# vco1_components.net
KiCad netlist of a schematic drawn in EAGLE
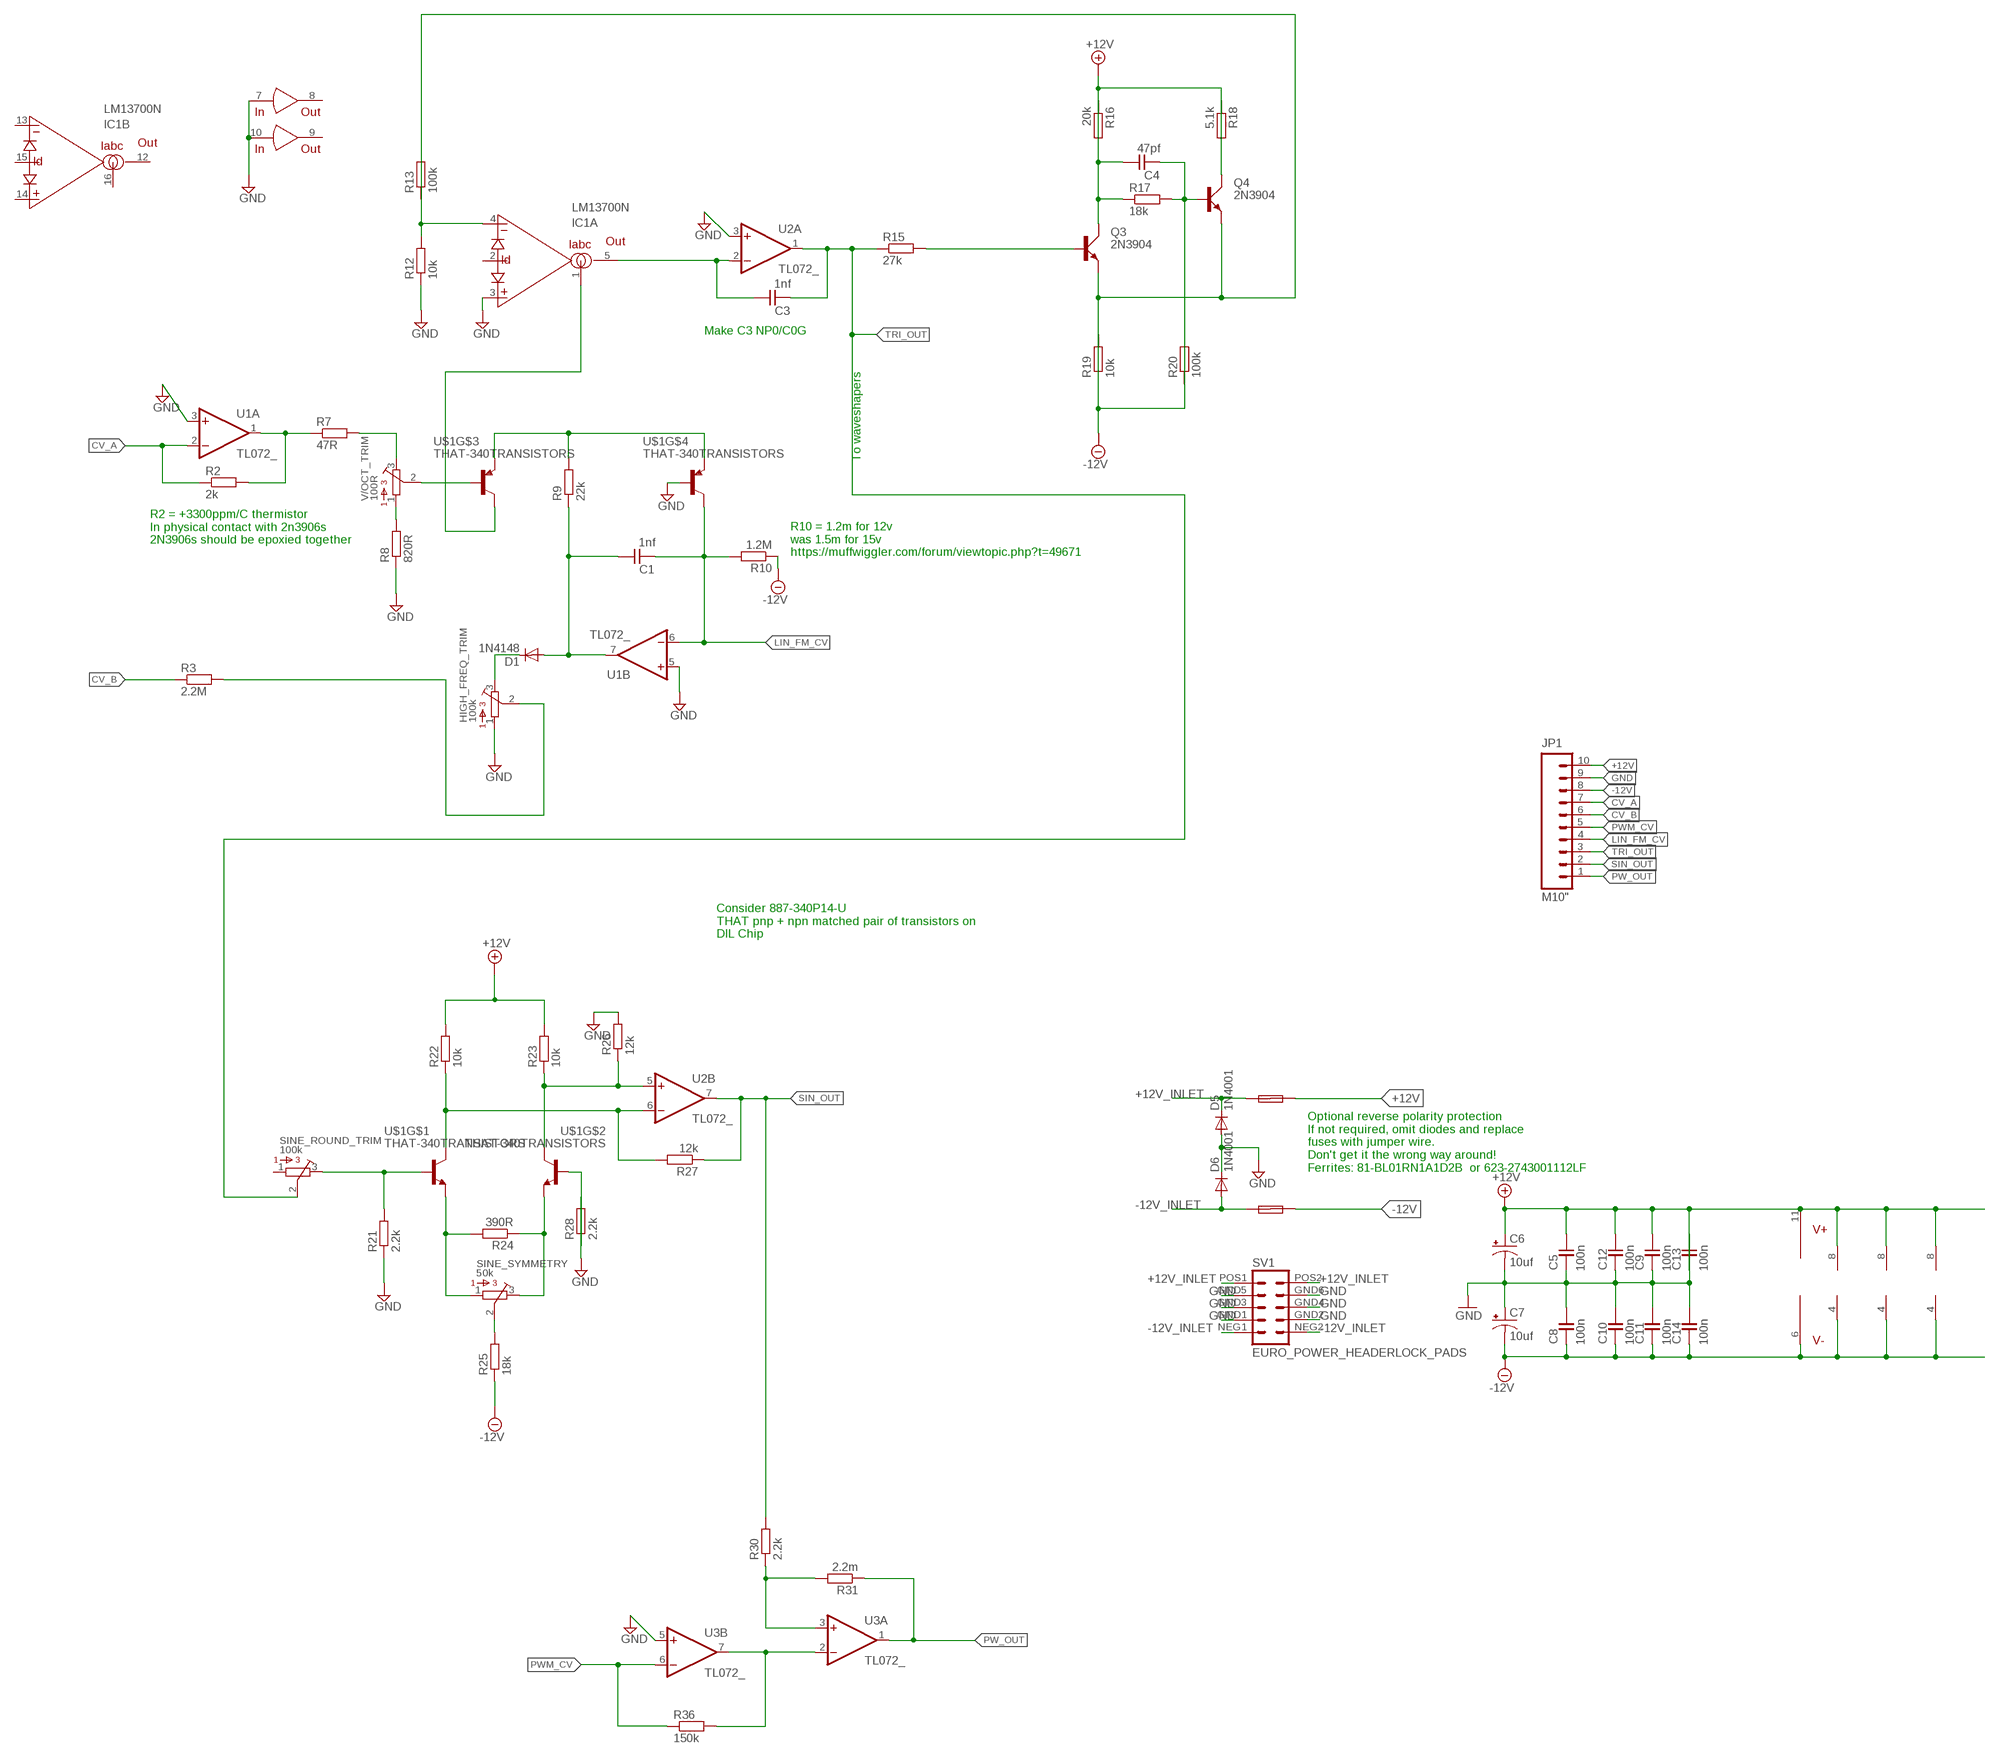
[diagram p0: schematic, sheet 1]

(export (version "E")
  (design (tool "Eeschema 10.0.6"))
  (components
    (comp (ref "C1")
      (value "1nf")
      (footprint "eagle-import:C050-024X044")
      (libsource (lib "eagle-import") (part "C-EU050-024X044"))
    )
    (comp (ref "C3")
      (value "1nf")
      (footprint "eagle-import:C050-024X044")
      (libsource (lib "eagle-import") (part "C-EU050-024X044"))
    )
    (comp (ref "C4")
      (value "47pf")
      (footprint "eagle-import:C050-024X044")
      (libsource (lib "eagle-import") (part "C-EU050-024X044"))
    )
    (comp (ref "C5")
      (value "100n")
      (footprint "eagle-import:C050-024X044")
      (libsource (lib "eagle-import") (part "C-EU050-024X044"))
    )
    (comp (ref "C6")
      (value "10uf")
      (footprint "eagle-import:CPOL-RADIAL-10UF-25V")
      (libsource (lib "eagle-import") (part "CAP_POLPTH2"))
    )
    (comp (ref "C7")
      (value "10uf")
      (footprint "eagle-import:CPOL-RADIAL-10UF-25V")
      (libsource (lib "eagle-import") (part "CAP_POLPTH2"))
    )
    (comp (ref "C8")
      (value "100n")
      (footprint "eagle-import:C050-024X044")
      (libsource (lib "eagle-import") (part "C-EU050-024X044"))
    )
    (comp (ref "C9")
      (value "100n")
      (footprint "eagle-import:C050-024X044")
      (libsource (lib "eagle-import") (part "C-EU050-024X044"))
    )
    (comp (ref "C10")
      (value "100n")
      (footprint "eagle-import:C050-024X044")
      (libsource (lib "eagle-import") (part "C-EU050-024X044"))
    )
    (comp (ref "C11")
      (value "100n")
      (footprint "eagle-import:C050-024X044")
      (libsource (lib "eagle-import") (part "C-EU050-024X044"))
    )
    (comp (ref "C12")
      (value "100n")
      (footprint "eagle-import:C050-024X044")
      (libsource (lib "eagle-import") (part "C-EU050-024X044"))
    )
    (comp (ref "C13")
      (value "100n")
      (footprint "eagle-import:C050-024X044")
      (libsource (lib "eagle-import") (part "C-EU050-024X044"))
    )
    (comp (ref "C14")
      (value "100n")
      (footprint "eagle-import:C050-024X044")
      (libsource (lib "eagle-import") (part "C-EU050-024X044"))
    )
    (comp (ref "D1")
      (value "1N4148")
      (footprint "eagle-import:DO35-7")
      (libsource (lib "eagle-import") (part "SMALL_DIODEDO35-7"))
    )
    (comp (ref "D5")
      (value "1N4001")
      (footprint "eagle-import:DO41-10")
      (libsource (lib "eagle-import") (part "1N4004"))
    )
    (comp (ref "D6")
      (value "1N4001")
      (footprint "eagle-import:DO41-10")
      (libsource (lib "eagle-import") (part "1N4004"))
    )
    (comp (ref "F1")
      (value "FUSE")
      (footprint "eagle-import:C050H075X075")
      (libsource (lib "eagle-import") (part "PTC_FUSEPOLY_FUSE"))
    )
    (comp (ref "F2")
      (value "FUSE")
      (footprint "eagle-import:C050H075X075")
      (libsource (lib "eagle-import") (part "PTC_FUSEPOLY_FUSE"))
    )
    (comp (ref "HIGH_FREQ_TRIM")
      (value "100k")
      (footprint "eagle-import:BOURNS_3362P_TRIMMER")
      (libsource (lib "eagle-import") (part "BOURNS_3362P_TRIMMERP"))
    )
    (comp (ref "IC1")
      (value "LM13700N")
      (footprint "eagle-import:DIL16")
      (libsource (lib "eagle-import") (part "LM13700N"))
    )
    (comp (ref "JP1")
      (value "M10\"")
      (footprint "eagle-import:1X10")
      (libsource (lib "eagle-import") (part "M10{dblquote}"))
    )
    (comp (ref "Q3")
      (value "2N3904")
      (footprint "eagle-import:TO92D")
      (libsource (lib "eagle-import") (part "2N3904"))
    )
    (comp (ref "Q4")
      (value "2N3904")
      (footprint "eagle-import:TO92D")
      (libsource (lib "eagle-import") (part "2N3904"))
    )
    (comp (ref "R2")
      (value "2k")
      (footprint "eagle-import:7MM_RESISTOR")
      (libsource (lib "eagle-import") (part "RESISTOR7MM"))
    )
    (comp (ref "R3")
      (value "2.2M")
      (footprint "eagle-import:7MM_RESISTOR")
      (libsource (lib "eagle-import") (part "RESISTOR7MM"))
    )
    (comp (ref "R7")
      (value "47R")
      (footprint "eagle-import:7MM_RESISTOR")
      (libsource (lib "eagle-import") (part "RESISTOR7MM"))
    )
    (comp (ref "R8")
      (value "820R")
      (footprint "eagle-import:7MM_RESISTOR")
      (libsource (lib "eagle-import") (part "RESISTOR7MM"))
    )
    (comp (ref "R9")
      (value "22k")
      (footprint "eagle-import:7MM_RESISTOR")
      (libsource (lib "eagle-import") (part "RESISTOR7MM"))
    )
    (comp (ref "R10")
      (value "1.2M")
      (footprint "eagle-import:7MM_RESISTOR")
      (libsource (lib "eagle-import") (part "RESISTOR7MM"))
    )
    (comp (ref "R12")
      (value "10k")
      (footprint "eagle-import:7MM_RESISTOR")
      (libsource (lib "eagle-import") (part "RESISTOR7MM"))
    )
    (comp (ref "R13")
      (value "100k")
      (footprint "eagle-import:7MM_RESISTOR")
      (libsource (lib "eagle-import") (part "RESISTOR7MM"))
    )
    (comp (ref "R15")
      (value "27k")
      (footprint "eagle-import:7MM_RESISTOR")
      (libsource (lib "eagle-import") (part "RESISTOR7MM"))
    )
    (comp (ref "R16")
      (value "20k")
      (footprint "eagle-import:7MM_RESISTOR")
      (libsource (lib "eagle-import") (part "RESISTOR7MM"))
    )
    (comp (ref "R17")
      (value "18k")
      (footprint "eagle-import:7MM_RESISTOR")
      (libsource (lib "eagle-import") (part "RESISTOR7MM"))
    )
    (comp (ref "R18")
      (value "5.1k")
      (footprint "eagle-import:7MM_RESISTOR")
      (libsource (lib "eagle-import") (part "RESISTOR7MM"))
    )
    (comp (ref "R19")
      (value "10k")
      (footprint "eagle-import:7MM_RESISTOR")
      (libsource (lib "eagle-import") (part "RESISTOR7MM"))
    )
    (comp (ref "R20")
      (value "100k")
      (footprint "eagle-import:7MM_RESISTOR")
      (libsource (lib "eagle-import") (part "RESISTOR7MM"))
    )
    (comp (ref "R21")
      (value "2.2k")
      (footprint "eagle-import:7MM_RESISTOR")
      (libsource (lib "eagle-import") (part "RESISTOR7MM"))
    )
    (comp (ref "R22")
      (value "10k")
      (footprint "eagle-import:7MM_RESISTOR")
      (libsource (lib "eagle-import") (part "RESISTOR7MM"))
    )
    (comp (ref "R23")
      (value "10k")
      (footprint "eagle-import:7MM_RESISTOR")
      (libsource (lib "eagle-import") (part "RESISTOR7MM"))
    )
    (comp (ref "R24")
      (value "390R")
      (footprint "eagle-import:7MM_RESISTOR")
      (libsource (lib "eagle-import") (part "RESISTOR7MM"))
    )
    (comp (ref "R25")
      (value "18k")
      (footprint "eagle-import:7MM_RESISTOR")
      (libsource (lib "eagle-import") (part "RESISTOR7MM"))
    )
    (comp (ref "R26")
      (value "12k")
      (footprint "eagle-import:7MM_RESISTOR")
      (libsource (lib "eagle-import") (part "RESISTOR7MM"))
    )
    (comp (ref "R27")
      (value "12k")
      (footprint "eagle-import:7MM_RESISTOR")
      (libsource (lib "eagle-import") (part "RESISTOR7MM"))
    )
    (comp (ref "R28")
      (value "2.2k")
      (footprint "eagle-import:7MM_RESISTOR")
      (libsource (lib "eagle-import") (part "RESISTOR7MM"))
    )
    (comp (ref "R30")
      (value "2.2k")
      (footprint "eagle-import:7MM_RESISTOR")
      (libsource (lib "eagle-import") (part "RESISTOR7MM"))
    )
    (comp (ref "R31")
      (value "2.2m")
      (footprint "eagle-import:7MM_RESISTOR")
      (libsource (lib "eagle-import") (part "RESISTOR7MM"))
    )
    (comp (ref "R36")
      (value "150k")
      (footprint "eagle-import:7MM_RESISTOR")
      (libsource (lib "eagle-import") (part "RESISTOR7MM"))
    )
    (comp (ref "SINE_ROUND_TRIM")
      (value "100k")
      (footprint "eagle-import:BOURNS_3362P_TRIMMER")
      (libsource (lib "eagle-import") (part "BOURNS_3362P_TRIMMERP"))
    )
    (comp (ref "SINE_SYMMETRY")
      (value "50k")
      (footprint "eagle-import:BOURNS_3362P_TRIMMER")
      (libsource (lib "eagle-import") (part "BOURNS_3362P_TRIMMERP"))
    )
    (comp (ref "SV1")
      (value "EURO_POWER_HEADERLOCK_PADS")
      (footprint "eagle-import:EURO_PWR_HEADER_LOCK")
      (libsource (lib "eagle-import") (part "EURO_POWER_HEADERLOCK_PADS"))
    )
    (comp (ref "U$1")
      (value "THAT-340TRANSISTORS")
      (footprint "eagle-import:THAT340")
      (libsource (lib "eagle-import") (part "THAT-340TRANSISTORS"))
    )
    (comp (ref "U1")
      (value "TL072_")
      (footprint "eagle-import:DIL08")
      (libsource (lib "eagle-import") (part "TL072_"))
    )
    (comp (ref "U2")
      (value "TL072_")
      (footprint "eagle-import:DIL08")
      (libsource (lib "eagle-import") (part "TL072_"))
    )
    (comp (ref "U3")
      (value "TL072_")
      (footprint "eagle-import:DIL08")
      (libsource (lib "eagle-import") (part "TL072_"))
    )
    (comp (ref "V/OCT_TRIM")
      (value "100R")
      (footprint "eagle-import:BOURNS_3362P_TRIMMER")
      (libsource (lib "eagle-import") (part "BOURNS_3362P_TRIMMERP"))
    )
  )
  (nets
    (net (code "1") (name "+12V") (class "Default")
      (node (ref "C12") (pin "1") (pinfunction "1_1") (pintype "passive"))
      (node (ref "C13") (pin "2") (pinfunction "2_2") (pintype "passive"))
      (node (ref "C5") (pin "1") (pinfunction "1_1") (pintype "passive"))
      (node (ref "C6") (pin "1") (pinfunction "+_1") (pintype "passive"))
      (node (ref "C9") (pin "1") (pinfunction "1_1") (pintype "passive"))
      (node (ref "F1") (pin "2") (pinfunction "P$2_2") (pintype "bidirectional"))
      (node (ref "IC1") (pin "11") (pinfunction "V+_11") (pintype "bidirectional"))
      (node (ref "JP1") (pin "10") (pinfunction "10_10") (pintype "passive"))
      (node (ref "R16") (pin "2") (pinfunction "2_2") (pintype "passive"))
      (node (ref "R18") (pin "2") (pinfunction "2_2") (pintype "passive"))
      (node (ref "R22") (pin "2") (pinfunction "2_2") (pintype "passive"))
      (node (ref "R23") (pin "2") (pinfunction "2_2") (pintype "passive"))
      (node (ref "U1") (pin "8") (pinfunction "V+_8") (pintype "power_in"))
      (node (ref "U2") (pin "8") (pinfunction "V+_8") (pintype "power_in"))
      (node (ref "U3") (pin "8") (pinfunction "V+_8") (pintype "power_in"))
    )
    (net (code "2") (name "-12V") (class "Default")
      (node (ref "C10") (pin "2") (pinfunction "2_2") (pintype "passive"))
      (node (ref "C11") (pin "2") (pinfunction "2_2") (pintype "passive"))
      (node (ref "C14") (pin "2") (pinfunction "2_2") (pintype "passive"))
      (node (ref "C7") (pin "2") (pinfunction "-_2") (pintype "passive"))
      (node (ref "C8") (pin "2") (pinfunction "2_2") (pintype "passive"))
      (node (ref "F2") (pin "2") (pinfunction "P$2_2") (pintype "bidirectional"))
      (node (ref "IC1") (pin "6") (pinfunction "V-_6") (pintype "bidirectional"))
      (node (ref "JP1") (pin "8") (pinfunction "8_8") (pintype "passive"))
      (node (ref "R10") (pin "1") (pinfunction "1_1") (pintype "passive"))
      (node (ref "R19") (pin "2") (pinfunction "2_2") (pintype "passive"))
      (node (ref "R20") (pin "2") (pinfunction "2_2") (pintype "passive"))
      (node (ref "R25") (pin "1") (pinfunction "1_1") (pintype "passive"))
      (node (ref "U1") (pin "4") (pinfunction "V-_4") (pintype "power_in"))
      (node (ref "U2") (pin "4") (pinfunction "V-_4") (pintype "power_in"))
      (node (ref "U3") (pin "4") (pinfunction "V-_4") (pintype "power_in"))
    )
    (net (code "3") (name "/+12V_INLET") (class "Default")
      (node (ref "D5") (pin "C") (pinfunction "C_C") (pintype "passive"))
      (node (ref "F1") (pin "1") (pinfunction "P$1_1") (pintype "bidirectional"))
      (node (ref "SV1") (pin "POS1") (pinfunction "10_POS1") (pintype "passive"))
      (node (ref "SV1") (pin "POS2") (pinfunction "9_POS2") (pintype "passive"))
    )
    (net (code "4") (name "/-12V_INLET") (class "Default")
      (node (ref "D6") (pin "A") (pinfunction "A_A") (pintype "passive"))
      (node (ref "F2") (pin "1") (pinfunction "P$1_1") (pintype "bidirectional"))
      (node (ref "SV1") (pin "NEG1") (pinfunction "2_NEG1") (pintype "passive"))
      (node (ref "SV1") (pin "NEG2") (pinfunction "1_NEG2") (pintype "passive"))
    )
    (net (code "5") (name "CV_A") (class "Default")
      (node (ref "JP1") (pin "7") (pinfunction "7_7") (pintype "passive"))
      (node (ref "R2") (pin "1") (pinfunction "1_1") (pintype "passive"))
      (node (ref "U1") (pin "2") (pinfunction "-IN_2") (pintype "input"))
    )
    (net (code "6") (name "CV_B") (class "Default")
      (node (ref "JP1") (pin "6") (pinfunction "6_6") (pintype "passive"))
      (node (ref "R3") (pin "1") (pinfunction "1_1") (pintype "passive"))
    )
    (net (code "7") (name "GND") (class "Default")
      (node (ref "C10") (pin "1") (pinfunction "1_1") (pintype "passive"))
      (node (ref "C11") (pin "1") (pinfunction "1_1") (pintype "passive"))
      (node (ref "C12") (pin "2") (pinfunction "2_2") (pintype "passive"))
      (node (ref "C13") (pin "1") (pinfunction "1_1") (pintype "passive"))
      (node (ref "C14") (pin "1") (pinfunction "1_1") (pintype "passive"))
      (node (ref "C5") (pin "2") (pinfunction "2_2") (pintype "passive"))
      (node (ref "C6") (pin "2") (pinfunction "-_2") (pintype "passive"))
      (node (ref "C7") (pin "1") (pinfunction "+_1") (pintype "passive"))
      (node (ref "C8") (pin "1") (pinfunction "1_1") (pintype "passive"))
      (node (ref "C9") (pin "2") (pinfunction "2_2") (pintype "passive"))
      (node (ref "D5") (pin "A") (pinfunction "A_A") (pintype "passive"))
      (node (ref "D6") (pin "C") (pinfunction "C_C") (pintype "passive"))
      (node (ref "HIGH_FREQ_TRIM") (pin "1") (pinfunction "1_1") (pintype "passive"))
      (node (ref "IC1") (pin "10") (pinfunction "IN_10") (pintype "bidirectional"))
      (node (ref "IC1") (pin "3") (pinfunction "+IN_3") (pintype "bidirectional"))
      (node (ref "IC1") (pin "7") (pinfunction "IN_7") (pintype "bidirectional"))
      (node (ref "JP1") (pin "9") (pinfunction "9_9") (pintype "passive"))
      (node (ref "R12") (pin "1") (pinfunction "1_1") (pintype "passive"))
      (node (ref "R21") (pin "1") (pinfunction "1_1") (pintype "passive"))
      (node (ref "R26") (pin "2") (pinfunction "2_2") (pintype "passive"))
      (node (ref "R28") (pin "2") (pinfunction "2_2") (pintype "passive"))
      (node (ref "R8") (pin "1") (pinfunction "1_1") (pintype "passive"))
      (node (ref "SV1") (pin "GND1") (pinfunction "4_GND1") (pintype "passive"))
      (node (ref "SV1") (pin "GND2") (pinfunction "3_GND2") (pintype "passive"))
      (node (ref "SV1") (pin "GND3") (pinfunction "6_GND3") (pintype "passive"))
      (node (ref "SV1") (pin "GND4") (pinfunction "5_GND4") (pintype "passive"))
      (node (ref "SV1") (pin "GND5") (pinfunction "8_GND5") (pintype "passive"))
      (node (ref "SV1") (pin "GND6") (pinfunction "7_GND6") (pintype "passive"))
      (node (ref "U$1") (pin "9") (pinfunction "B_9") (pintype "passive"))
      (node (ref "U1") (pin "3") (pinfunction "+IN_3") (pintype "input"))
      (node (ref "U1") (pin "5") (pinfunction "+IN_5") (pintype "input"))
      (node (ref "U2") (pin "3") (pinfunction "+IN_3") (pintype "input"))
      (node (ref "U3") (pin "5") (pinfunction "+IN_5") (pintype "input"))
    )
    (net (code "8") (name "LIN_FM_CV") (class "Default")
      (node (ref "C1") (pin "2") (pinfunction "2_2") (pintype "passive"))
      (node (ref "JP1") (pin "4") (pinfunction "4_4") (pintype "passive"))
      (node (ref "R10") (pin "2") (pinfunction "2_2") (pintype "passive"))
      (node (ref "U$1") (pin "8") (pinfunction "C_8") (pintype "passive"))
      (node (ref "U1") (pin "6") (pinfunction "-IN_6") (pintype "input"))
    )
    (net (code "9") (name "Net-(C4-Pad1)") (class "Default")
      (node (ref "C4") (pin "1") (pinfunction "1_1") (pintype "passive"))
      (node (ref "Q3") (pin "C") (pinfunction "C_C") (pintype "passive"))
      (node (ref "R16") (pin "1") (pinfunction "1_1") (pintype "passive"))
      (node (ref "R17") (pin "1") (pinfunction "1_1") (pintype "passive"))
    )
    (net (code "10") (name "Net-(C4-Pad2)") (class "Default")
      (node (ref "C4") (pin "2") (pinfunction "2_2") (pintype "passive"))
      (node (ref "Q4") (pin "B") (pinfunction "B_B") (pintype "passive"))
      (node (ref "R17") (pin "2") (pinfunction "2_2") (pintype "passive"))
      (node (ref "R20") (pin "1") (pinfunction "1_1") (pintype "passive"))
    )
    (net (code "11") (name "Net-(D1-PadC)") (class "Default")
      (node (ref "D1") (pin "C") (pinfunction "C_C") (pintype "passive"))
      (node (ref "HIGH_FREQ_TRIM") (pin "3") (pinfunction "3_3") (pintype "passive"))
    )
    (net (code "12") (name "Net-(HIGH_FREQ_TRIM-Pad2)") (class "Default")
      (node (ref "HIGH_FREQ_TRIM") (pin "2") (pinfunction "2_2") (pintype "passive"))
      (node (ref "R3") (pin "2") (pinfunction "2_2") (pintype "passive"))
    )
    (net (code "13") (name "Net-(IC1A--IN)") (class "Default")
      (node (ref "IC1") (pin "4") (pinfunction "-IN_4") (pintype "bidirectional"))
      (node (ref "R12") (pin "2") (pinfunction "2_2") (pintype "passive"))
      (node (ref "R13") (pin "2") (pinfunction "2_2") (pintype "passive"))
    )
    (net (code "14") (name "Net-(IC1A-IABC)") (class "Default")
      (node (ref "IC1") (pin "1") (pinfunction "IABC_1") (pintype "bidirectional"))
      (node (ref "U$1") (pin "7") (pinfunction "C_7") (pintype "passive"))
    )
    (net (code "15") (name "Net-(IC1A-OUT)") (class "Default")
      (node (ref "C3") (pin "1") (pinfunction "1_1") (pintype "passive"))
      (node (ref "IC1") (pin "5") (pinfunction "OUT_5") (pintype "bidirectional"))
      (node (ref "U2") (pin "2") (pinfunction "-IN_2") (pintype "input"))
    )
    (net (code "16") (name "Net-(Q3-PadB)") (class "Default")
      (node (ref "Q3") (pin "B") (pinfunction "B_B") (pintype "passive"))
      (node (ref "R15") (pin "2") (pinfunction "2_2") (pintype "passive"))
    )
    (net (code "17") (name "Net-(Q3-PadE)") (class "Default")
      (node (ref "Q3") (pin "E") (pinfunction "E_E") (pintype "passive"))
      (node (ref "Q4") (pin "E") (pinfunction "E_E") (pintype "passive"))
      (node (ref "R13") (pin "1") (pinfunction "1_1") (pintype "passive"))
      (node (ref "R19") (pin "1") (pinfunction "1_1") (pintype "passive"))
    )
    (net (code "18") (name "Net-(Q4-PadC)") (class "Default")
      (node (ref "Q4") (pin "C") (pinfunction "C_C") (pintype "passive"))
      (node (ref "R18") (pin "1") (pinfunction "1_1") (pintype "passive"))
    )
    (net (code "19") (name "Net-(R7-Pad2)") (class "Default")
      (node (ref "R7") (pin "2") (pinfunction "2_2") (pintype "passive"))
      (node (ref "V/OCT_TRIM") (pin "3") (pinfunction "3_3") (pintype "passive"))
    )
    (net (code "20") (name "Net-(R8-Pad2)") (class "Default")
      (node (ref "R8") (pin "2") (pinfunction "2_2") (pintype "passive"))
      (node (ref "V/OCT_TRIM") (pin "1") (pinfunction "1_1") (pintype "passive"))
    )
    (net (code "21") (name "Net-(R25-Pad2)") (class "Default")
      (node (ref "R25") (pin "2") (pinfunction "2_2") (pintype "passive"))
      (node (ref "SINE_SYMMETRY") (pin "2") (pinfunction "2_2") (pintype "passive"))
    )
    (net (code "22") (name "Net-(U$1A-B)") (class "Default")
      (node (ref "R21") (pin "2") (pinfunction "2_2") (pintype "passive"))
      (node (ref "SINE_ROUND_TRIM") (pin "3") (pinfunction "3_3") (pintype "passive"))
      (node (ref "U$1") (pin "2") (pinfunction "B_2") (pintype "passive"))
    )
    (net (code "23") (name "Net-(U$1A-C)") (class "Default")
      (node (ref "R22") (pin "1") (pinfunction "1_1") (pintype "passive"))
      (node (ref "R27") (pin "2") (pinfunction "2_2") (pintype "passive"))
      (node (ref "U$1") (pin "1") (pinfunction "C_1") (pintype "passive"))
      (node (ref "U2") (pin "6") (pinfunction "-IN_6") (pintype "input"))
    )
    (net (code "24") (name "Net-(U$1A-E)") (class "Default")
      (node (ref "R24") (pin "2") (pinfunction "2_2") (pintype "passive"))
      (node (ref "SINE_SYMMETRY") (pin "1") (pinfunction "1_1") (pintype "passive"))
      (node (ref "U$1") (pin "3") (pinfunction "E_3") (pintype "passive"))
    )
    (net (code "25") (name "Net-(U$1B-B)") (class "Default")
      (node (ref "R28") (pin "1") (pinfunction "1_1") (pintype "passive"))
      (node (ref "U$1") (pin "13") (pinfunction "B_13") (pintype "passive"))
    )
    (net (code "26") (name "Net-(U$1B-C)") (class "Default")
      (node (ref "R23") (pin "1") (pinfunction "1_1") (pintype "passive"))
      (node (ref "R26") (pin "1") (pinfunction "1_1") (pintype "passive"))
      (node (ref "U$1") (pin "14") (pinfunction "C_14") (pintype "passive"))
      (node (ref "U2") (pin "5") (pinfunction "+IN_5") (pintype "input"))
    )
    (net (code "27") (name "Net-(U$1B-E)") (class "Default")
      (node (ref "R24") (pin "1") (pinfunction "1_1") (pintype "passive"))
      (node (ref "SINE_SYMMETRY") (pin "3") (pinfunction "3_3") (pintype "passive"))
      (node (ref "U$1") (pin "12") (pinfunction "E_12") (pintype "passive"))
    )
    (net (code "28") (name "Net-(U$1C-B)") (class "Default")
      (node (ref "U$1") (pin "6") (pinfunction "B_6") (pintype "passive"))
      (node (ref "V/OCT_TRIM") (pin "2") (pinfunction "2_2") (pintype "passive"))
    )
    (net (code "29") (name "Net-(U$1C-E)") (class "Default")
      (node (ref "R9") (pin "2") (pinfunction "2_2") (pintype "passive"))
      (node (ref "U$1") (pin "10") (pinfunction "E_10") (pintype "passive"))
      (node (ref "U$1") (pin "5") (pinfunction "E_5") (pintype "passive"))
    )
    (net (code "30") (name "Net-(U1A-OUT)") (class "Default")
      (node (ref "R2") (pin "2") (pinfunction "2_2") (pintype "passive"))
      (node (ref "R7") (pin "1") (pinfunction "1_1") (pintype "passive"))
      (node (ref "U1") (pin "1") (pinfunction "OUT_1") (pintype "output"))
    )
    (net (code "31") (name "Net-(U1B-OUT)") (class "Default")
      (node (ref "C1") (pin "1") (pinfunction "1_1") (pintype "passive"))
      (node (ref "D1") (pin "A") (pinfunction "A_A") (pintype "passive"))
      (node (ref "R9") (pin "1") (pinfunction "1_1") (pintype "passive"))
      (node (ref "U1") (pin "7") (pinfunction "OUT_7") (pintype "output"))
    )
    (net (code "32") (name "Net-(U3A-+IN)") (class "Default")
      (node (ref "R30") (pin "1") (pinfunction "1_1") (pintype "passive"))
      (node (ref "R31") (pin "2") (pinfunction "2_2") (pintype "passive"))
      (node (ref "U3") (pin "3") (pinfunction "+IN_3") (pintype "input"))
    )
    (net (code "33") (name "Net-(U3A--IN)") (class "Default")
      (node (ref "R36") (pin "2") (pinfunction "2_2") (pintype "passive"))
      (node (ref "U3") (pin "2") (pinfunction "-IN_2") (pintype "input"))
      (node (ref "U3") (pin "7") (pinfunction "OUT_7") (pintype "output"))
    )
    (net (code "34") (name "PWM_CV") (class "Default")
      (node (ref "JP1") (pin "5") (pinfunction "5_5") (pintype "passive"))
      (node (ref "R36") (pin "1") (pinfunction "1_1") (pintype "passive"))
      (node (ref "U3") (pin "6") (pinfunction "-IN_6") (pintype "input"))
    )
    (net (code "35") (name "PW_OUT") (class "Default")
      (node (ref "JP1") (pin "1") (pinfunction "1_1") (pintype "passive"))
      (node (ref "R31") (pin "1") (pinfunction "1_1") (pintype "passive"))
      (node (ref "U3") (pin "1") (pinfunction "OUT_1") (pintype "output"))
    )
    (net (code "36") (name "SIN_OUT") (class "Default")
      (node (ref "JP1") (pin "2") (pinfunction "2_2") (pintype "passive"))
      (node (ref "R27") (pin "1") (pinfunction "1_1") (pintype "passive"))
      (node (ref "R30") (pin "2") (pinfunction "2_2") (pintype "passive"))
      (node (ref "U2") (pin "7") (pinfunction "OUT_7") (pintype "output"))
    )
    (net (code "37") (name "TRI_OUT") (class "Default")
      (node (ref "C3") (pin "2") (pinfunction "2_2") (pintype "passive"))
      (node (ref "JP1") (pin "3") (pinfunction "3_3") (pintype "passive"))
      (node (ref "R15") (pin "1") (pinfunction "1_1") (pintype "passive"))
      (node (ref "SINE_ROUND_TRIM") (pin "2") (pinfunction "2_2") (pintype "passive"))
      (node (ref "U2") (pin "1") (pinfunction "OUT_1") (pintype "output"))
    )
    (net (code "38") (name "unconnected-(IC1A-ID-Pad2)") (class "Default")
      (node (ref "IC1") (pin "2") (pinfunction "ID_2") (pintype "bidirectional"))
    )
    (net (code "39") (name "unconnected-(IC1B-+IN-Pad14)") (class "Default")
      (node (ref "IC1") (pin "14") (pinfunction "+IN_14") (pintype "bidirectional"))
    )
    (net (code "40") (name "unconnected-(IC1B--IN-Pad13)") (class "Default")
      (node (ref "IC1") (pin "13") (pinfunction "-IN_13") (pintype "bidirectional"))
    )
    (net (code "41") (name "unconnected-(IC1B-IABC-Pad16)") (class "Default")
      (node (ref "IC1") (pin "16") (pinfunction "IABC_16") (pintype "bidirectional"))
    )
    (net (code "42") (name "unconnected-(IC1B-ID-Pad15)") (class "Default")
      (node (ref "IC1") (pin "15") (pinfunction "ID_15") (pintype "bidirectional"))
    )
    (net (code "43") (name "unconnected-(IC1B-OUT-Pad12)") (class "Default")
      (node (ref "IC1") (pin "12") (pinfunction "OUT_12") (pintype "bidirectional"))
    )
    (net (code "44") (name "unconnected-(IC1C-OUT-Pad8)") (class "Default")
      (node (ref "IC1") (pin "8") (pinfunction "OUT_8") (pintype "bidirectional"))
    )
    (net (code "45") (name "unconnected-(IC1D-OUT-Pad9)") (class "Default")
      (node (ref "IC1") (pin "9") (pinfunction "OUT_9") (pintype "bidirectional"))
    )
    (net (code "46") (name "unconnected-(SINE_ROUND_TRIM-Pad1)") (class "Default")
      (node (ref "SINE_ROUND_TRIM") (pin "1") (pinfunction "1_1") (pintype "passive"))
    )
  )
)
